# CMOS_MUSIC_I_Schematic_2016_Edition.net
KiCad netlist of a schematic drawn in EAGLE
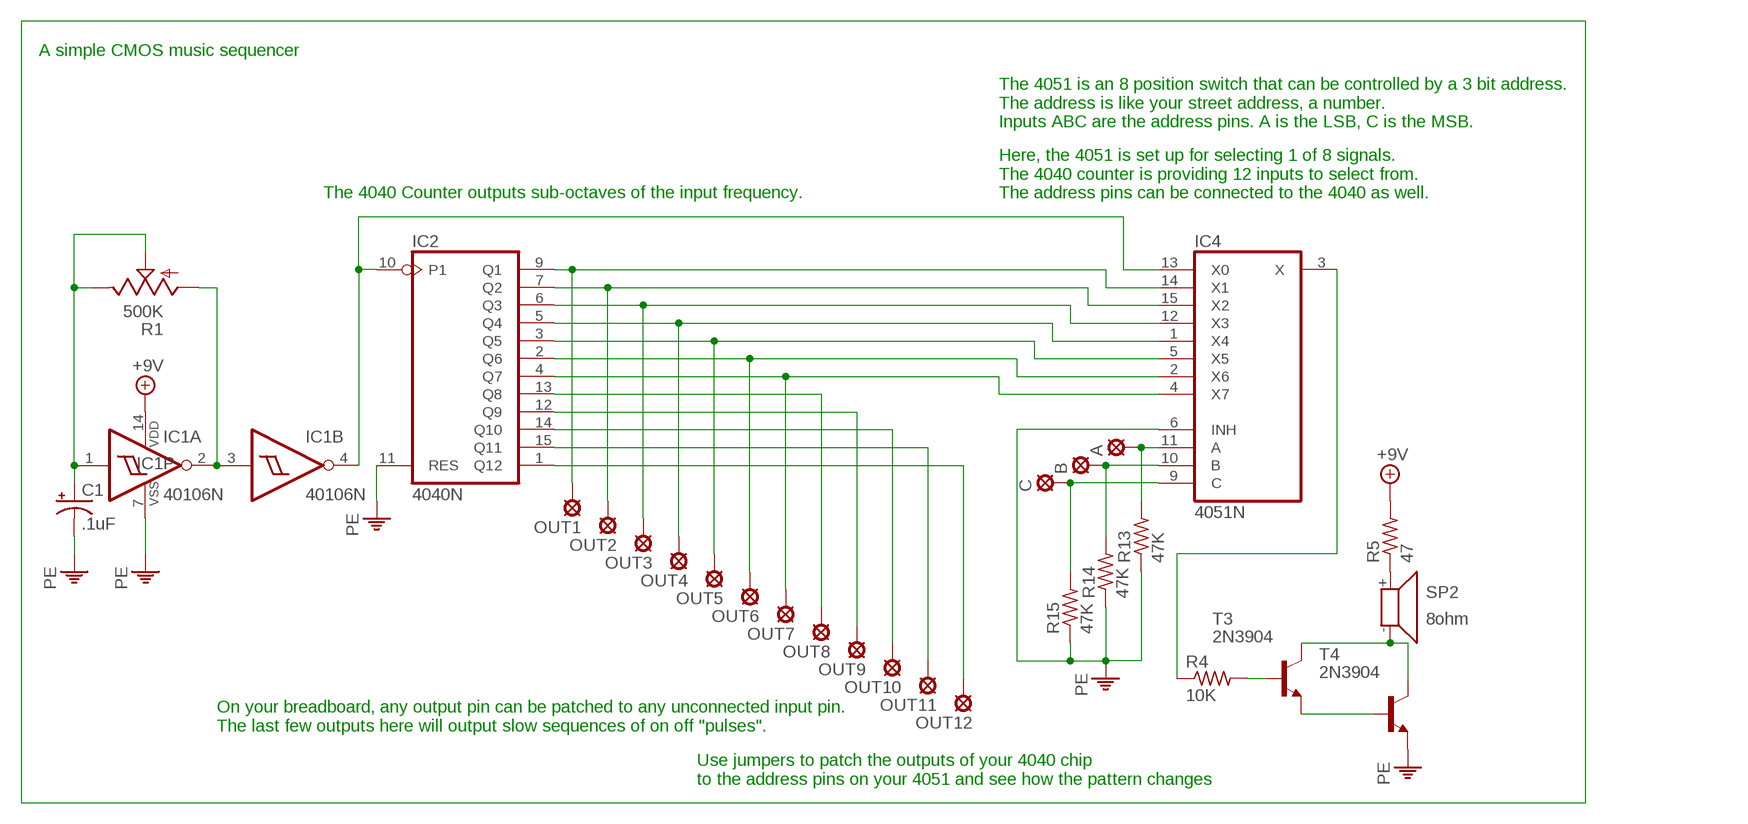
[diagram p0: schematic, sheet 1]
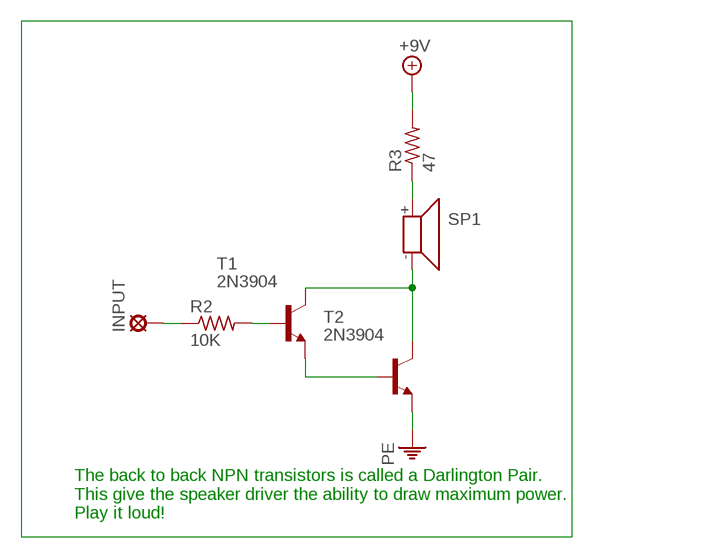
[diagram p1: schematic, sheet 2]

(export (version "E")
  (design (tool "Eeschema 10.0.6"))
  (components
    (comp (ref "INPUT")
      (value "MCS10B")
      (footprint "eagle-import:MCS10B")
      (libsource (lib "eagle-import") (part "MCS10B"))
    )
    (comp (ref "R2")
      (value "10K")
      (footprint "eagle-import:0204_7")
      (libsource (lib "eagle-import") (part "R-US_0204/7"))
    )
    (comp (ref "R3")
      (value "47")
      (footprint "eagle-import:0204_7")
      (libsource (lib "eagle-import") (part "R-US_0204/7"))
    )
    (comp (ref "SP1")
      (value "SMS-1308MS-2-R")
      (footprint "eagle-import:SMS-1308MS-2-R")
      (libsource (lib "eagle-import") (part "SMS-1308MS-2-R"))
    )
    (comp (ref "T1")
      (value "2N3904")
      (footprint "eagle-import:TO92")
      (libsource (lib "eagle-import") (part "2N3904"))
    )
    (comp (ref "T2")
      (value "2N3904")
      (footprint "eagle-import:TO92")
      (libsource (lib "eagle-import") (part "2N3904"))
    )
    (comp (ref "A")
      (value "MCS10B")
      (footprint "eagle-import:MCS10B")
      (libsource (lib "eagle-import") (part "MCS10B"))
    )
    (comp (ref "B")
      (value "MCS10B")
      (footprint "eagle-import:MCS10B")
      (libsource (lib "eagle-import") (part "MCS10B"))
    )
    (comp (ref "C")
      (value "MCS10B")
      (footprint "eagle-import:MCS10B")
      (libsource (lib "eagle-import") (part "MCS10B"))
    )
    (comp (ref "C1")
      (value ".1uF")
      (footprint "eagle-import:E2,5-6E")
      (libsource (lib "eagle-import") (part "CPOL-USE2,5-6E"))
    )
    (comp (ref "IC1")
      (value "40106N")
      (footprint "eagle-import:DIL14")
      (libsource (lib "eagle-import") (part "40106N"))
    )
    (comp (ref "IC2")
      (value "4040N")
      (footprint "eagle-import:DIL16")
      (libsource (lib "eagle-import") (part "4040N"))
    )
    (comp (ref "IC4")
      (value "4051N")
      (footprint "eagle-import:DIL16")
      (libsource (lib "eagle-import") (part "4051N"))
    )
    (comp (ref "OUT1")
      (value "MCS10B")
      (footprint "eagle-import:MCS10B")
      (libsource (lib "eagle-import") (part "MCS10B"))
    )
    (comp (ref "OUT2")
      (value "MCS10B")
      (footprint "eagle-import:MCS10B")
      (libsource (lib "eagle-import") (part "MCS10B"))
    )
    (comp (ref "OUT3")
      (value "MCS10B")
      (footprint "eagle-import:MCS10B")
      (libsource (lib "eagle-import") (part "MCS10B"))
    )
    (comp (ref "OUT4")
      (value "MCS10B")
      (footprint "eagle-import:MCS10B")
      (libsource (lib "eagle-import") (part "MCS10B"))
    )
    (comp (ref "OUT5")
      (value "MCS10B")
      (footprint "eagle-import:MCS10B")
      (libsource (lib "eagle-import") (part "MCS10B"))
    )
    (comp (ref "OUT6")
      (value "MCS10B")
      (footprint "eagle-import:MCS10B")
      (libsource (lib "eagle-import") (part "MCS10B"))
    )
    (comp (ref "OUT7")
      (value "MCS10B")
      (footprint "eagle-import:MCS10B")
      (libsource (lib "eagle-import") (part "MCS10B"))
    )
    (comp (ref "OUT8")
      (value "MCS10B")
      (footprint "eagle-import:MCS10B")
      (libsource (lib "eagle-import") (part "MCS10B"))
    )
    (comp (ref "OUT9")
      (value "MCS10B")
      (footprint "eagle-import:MCS10B")
      (libsource (lib "eagle-import") (part "MCS10B"))
    )
    (comp (ref "OUT10")
      (value "MCS10B")
      (footprint "eagle-import:MCS10B")
      (libsource (lib "eagle-import") (part "MCS10B"))
    )
    (comp (ref "OUT11")
      (value "MCS10B")
      (footprint "eagle-import:MCS10B")
      (libsource (lib "eagle-import") (part "MCS10B"))
    )
    (comp (ref "OUT12")
      (value "MCS10B")
      (footprint "eagle-import:MCS10B")
      (libsource (lib "eagle-import") (part "MCS10B"))
    )
    (comp (ref "R1")
      (value "500K")
      (footprint "eagle-import:EVUF")
      (libsource (lib "eagle-import") (part "US-EVUAF2"))
    )
    (comp (ref "R4")
      (value "10K")
      (footprint "eagle-import:0204_7")
      (libsource (lib "eagle-import") (part "R-US_0204/7"))
    )
    (comp (ref "R5")
      (value "47")
      (footprint "eagle-import:0204_7")
      (libsource (lib "eagle-import") (part "R-US_0204/7"))
    )
    (comp (ref "R13")
      (value "47K")
      (footprint "eagle-import:0204_7")
      (libsource (lib "eagle-import") (part "R-US_0204/7"))
    )
    (comp (ref "R14")
      (value "47K")
      (footprint "eagle-import:0204_7")
      (libsource (lib "eagle-import") (part "R-US_0204/7"))
    )
    (comp (ref "R15")
      (value "47K")
      (footprint "eagle-import:0204_7")
      (libsource (lib "eagle-import") (part "R-US_0204/7"))
    )
    (comp (ref "SP2")
      (value "8ohm")
      (footprint "eagle-import:SMS-1308MS-2-R")
      (libsource (lib "eagle-import") (part "SMS-1308MS-2-R"))
    )
    (comp (ref "T3")
      (value "2N3904")
      (footprint "eagle-import:TO92")
      (libsource (lib "eagle-import") (part "2N3904"))
    )
    (comp (ref "T4")
      (value "2N3904")
      (footprint "eagle-import:TO92")
      (libsource (lib "eagle-import") (part "2N3904"))
    )
  )
  (nets
    (net (code "1") (name "+9V") (class "Default")
      (node (ref "IC1") (pin "14") (pinfunction "VDD_14") (pintype "power_in"))
      (node (ref "R3") (pin "2") (pinfunction "2_2") (pintype "passive"))
      (node (ref "R5") (pin "2") (pinfunction "2_2") (pintype "passive"))
    )
    (net (code "2") (name "Net-(IC1A-I)") (class "Default")
      (node (ref "C1") (pin "+") (pinfunction "+_+") (pintype "passive"))
      (node (ref "IC1") (pin "1") (pinfunction "I_1") (pintype "input"))
      (node (ref "R1") (pin "2") (pinfunction "S_2") (pintype "passive"))
      (node (ref "R1") (pin "3") (pinfunction "E_3") (pintype "passive"))
    )
    (net (code "3") (name "Net-(IC1A-O)") (class "Default")
      (node (ref "IC1") (pin "2") (pinfunction "O_2") (pintype "output"))
      (node (ref "IC1") (pin "3") (pinfunction "I_3") (pintype "input"))
      (node (ref "R1") (pin "1") (pinfunction "A_1") (pintype "passive"))
    )
    (net (code "4") (name "Net-(IC1B-O)") (class "Default")
      (node (ref "IC1") (pin "4") (pinfunction "O_4") (pintype "output"))
      (node (ref "IC2") (pin "10") (pinfunction "P1_10") (pintype "input"))
      (node (ref "IC4") (pin "13") (pinfunction "X0_13") (pintype "bidirectional"))
    )
    (net (code "5") (name "Net-(IC2A-Q1)") (class "Default")
      (node (ref "IC2") (pin "9") (pinfunction "Q1_9") (pintype "output"))
      (node (ref "IC4") (pin "14") (pinfunction "X1_14") (pintype "bidirectional"))
      (node (ref "OUT1") (pin "MP") (pinfunction "MP_MP") (pintype "passive"))
    )
    (net (code "6") (name "Net-(IC2A-Q2)") (class "Default")
      (node (ref "IC2") (pin "7") (pinfunction "Q2_7") (pintype "output"))
      (node (ref "IC4") (pin "15") (pinfunction "X2_15") (pintype "bidirectional"))
      (node (ref "OUT2") (pin "MP") (pinfunction "MP_MP") (pintype "passive"))
    )
    (net (code "7") (name "Net-(IC2A-Q3)") (class "Default")
      (node (ref "IC2") (pin "6") (pinfunction "Q3_6") (pintype "output"))
      (node (ref "IC4") (pin "12") (pinfunction "X3_12") (pintype "bidirectional"))
      (node (ref "OUT3") (pin "MP") (pinfunction "MP_MP") (pintype "passive"))
    )
    (net (code "8") (name "Net-(IC2A-Q4)") (class "Default")
      (node (ref "IC2") (pin "5") (pinfunction "Q4_5") (pintype "output"))
      (node (ref "IC4") (pin "1") (pinfunction "X4_1") (pintype "bidirectional"))
      (node (ref "OUT4") (pin "MP") (pinfunction "MP_MP") (pintype "passive"))
    )
    (net (code "9") (name "Net-(IC2A-Q5)") (class "Default")
      (node (ref "IC2") (pin "3") (pinfunction "Q5_3") (pintype "output"))
      (node (ref "IC4") (pin "5") (pinfunction "X5_5") (pintype "bidirectional"))
      (node (ref "OUT5") (pin "MP") (pinfunction "MP_MP") (pintype "passive"))
    )
    (net (code "10") (name "Net-(IC2A-Q6)") (class "Default")
      (node (ref "IC2") (pin "2") (pinfunction "Q6_2") (pintype "output"))
      (node (ref "IC4") (pin "2") (pinfunction "X6_2") (pintype "bidirectional"))
      (node (ref "OUT6") (pin "MP") (pinfunction "MP_MP") (pintype "passive"))
    )
    (net (code "11") (name "Net-(IC2A-Q7)") (class "Default")
      (node (ref "IC2") (pin "4") (pinfunction "Q7_4") (pintype "output"))
      (node (ref "IC4") (pin "4") (pinfunction "X7_4") (pintype "bidirectional"))
      (node (ref "OUT7") (pin "MP") (pinfunction "MP_MP") (pintype "passive"))
    )
    (net (code "12") (name "Net-(IC2A-Q8)") (class "Default")
      (node (ref "IC2") (pin "13") (pinfunction "Q8_13") (pintype "output"))
      (node (ref "OUT8") (pin "MP") (pinfunction "MP_MP") (pintype "passive"))
    )
    (net (code "13") (name "Net-(IC2A-Q9)") (class "Default")
      (node (ref "IC2") (pin "12") (pinfunction "Q9_12") (pintype "output"))
      (node (ref "OUT9") (pin "MP") (pinfunction "MP_MP") (pintype "passive"))
    )
    (net (code "14") (name "Net-(IC2A-Q10)") (class "Default")
      (node (ref "IC2") (pin "14") (pinfunction "Q10_14") (pintype "output"))
      (node (ref "OUT10") (pin "MP") (pinfunction "MP_MP") (pintype "passive"))
    )
    (net (code "15") (name "Net-(IC2A-Q11)") (class "Default")
      (node (ref "IC2") (pin "15") (pinfunction "Q11_15") (pintype "output"))
      (node (ref "OUT11") (pin "MP") (pinfunction "MP_MP") (pintype "passive"))
    )
    (net (code "16") (name "Net-(IC2A-Q12)") (class "Default")
      (node (ref "IC2") (pin "1") (pinfunction "Q12_1") (pintype "output"))
      (node (ref "OUT12") (pin "MP") (pinfunction "MP_MP") (pintype "passive"))
    )
    (net (code "17") (name "Net-(IC4A-A)") (class "Default")
      (node (ref "A") (pin "MP") (pinfunction "MP_MP") (pintype "passive"))
      (node (ref "IC4") (pin "11") (pinfunction "A_11") (pintype "input"))
      (node (ref "R13") (pin "2") (pinfunction "2_2") (pintype "passive"))
    )
    (net (code "18") (name "Net-(IC4A-B)") (class "Default")
      (node (ref "B") (pin "MP") (pinfunction "MP_MP") (pintype "passive"))
      (node (ref "IC4") (pin "10") (pinfunction "B_10") (pintype "input"))
      (node (ref "R14") (pin "2") (pinfunction "2_2") (pintype "passive"))
    )
    (net (code "19") (name "Net-(IC4A-C)") (class "Default")
      (node (ref "C") (pin "MP") (pinfunction "MP_MP") (pintype "passive"))
      (node (ref "IC4") (pin "9") (pinfunction "C_9") (pintype "input"))
      (node (ref "R15") (pin "2") (pinfunction "2_2") (pintype "passive"))
    )
    (net (code "20") (name "Net-(IC4A-X)") (class "Default")
      (node (ref "IC4") (pin "3") (pinfunction "X_3") (pintype "bidirectional"))
      (node (ref "R4") (pin "1") (pinfunction "1_1") (pintype "passive"))
    )
    (net (code "21") (name "Net-(INPUT-PadMP)") (class "Default")
      (node (ref "INPUT") (pin "MP") (pinfunction "MP_MP") (pintype "passive"))
      (node (ref "R2") (pin "1") (pinfunction "1_1") (pintype "passive"))
    )
    (net (code "22") (name "Net-(SP1-1)") (class "Default")
      (node (ref "R3") (pin "1") (pinfunction "1_1") (pintype "passive"))
      (node (ref "SP1") (pin "+") (pinfunction "1_+") (pintype "passive"))
    )
    (net (code "23") (name "Net-(SP1-2)") (class "Default")
      (node (ref "SP1") (pin "-") (pinfunction "2_-") (pintype "passive"))
      (node (ref "T1") (pin "1") (pinfunction "C_1") (pintype "passive"))
      (node (ref "T2") (pin "1") (pinfunction "C_1") (pintype "passive"))
    )
    (net (code "24") (name "Net-(SP2-1)") (class "Default")
      (node (ref "R5") (pin "1") (pinfunction "1_1") (pintype "passive"))
      (node (ref "SP2") (pin "+") (pinfunction "1_+") (pintype "passive"))
    )
    (net (code "25") (name "Net-(SP2-2)") (class "Default")
      (node (ref "SP2") (pin "-") (pinfunction "2_-") (pintype "passive"))
      (node (ref "T3") (pin "1") (pinfunction "C_1") (pintype "passive"))
      (node (ref "T4") (pin "1") (pinfunction "C_1") (pintype "passive"))
    )
    (net (code "26") (name "Net-(T1-B)") (class "Default")
      (node (ref "R2") (pin "2") (pinfunction "2_2") (pintype "passive"))
      (node (ref "T1") (pin "2") (pinfunction "B_2") (pintype "passive"))
    )
    (net (code "27") (name "Net-(T1-E)") (class "Default")
      (node (ref "T1") (pin "3") (pinfunction "E_3") (pintype "passive"))
      (node (ref "T2") (pin "2") (pinfunction "B_2") (pintype "passive"))
    )
    (net (code "28") (name "Net-(T3-B)") (class "Default")
      (node (ref "R4") (pin "2") (pinfunction "2_2") (pintype "passive"))
      (node (ref "T3") (pin "2") (pinfunction "B_2") (pintype "passive"))
    )
    (net (code "29") (name "Net-(T3-E)") (class "Default")
      (node (ref "T3") (pin "3") (pinfunction "E_3") (pintype "passive"))
      (node (ref "T4") (pin "2") (pinfunction "B_2") (pintype "passive"))
    )
    (net (code "30") (name "PE") (class "Default")
      (node (ref "C1") (pin "-") (pinfunction "-_-") (pintype "passive"))
      (node (ref "IC1") (pin "7") (pinfunction "VSS_7") (pintype "power_in"))
      (node (ref "IC2") (pin "11") (pinfunction "RES_11") (pintype "input"))
      (node (ref "IC4") (pin "6") (pinfunction "INH_6") (pintype "input"))
      (node (ref "R13") (pin "1") (pinfunction "1_1") (pintype "passive"))
      (node (ref "R14") (pin "1") (pinfunction "1_1") (pintype "passive"))
      (node (ref "R15") (pin "1") (pinfunction "1_1") (pintype "passive"))
      (node (ref "T2") (pin "3") (pinfunction "E_3") (pintype "passive"))
      (node (ref "T4") (pin "3") (pinfunction "E_3") (pintype "passive"))
    )
  )
)
